# hv_io_rms.net
KiCad netlist of a schematic drawn in Altium Designer
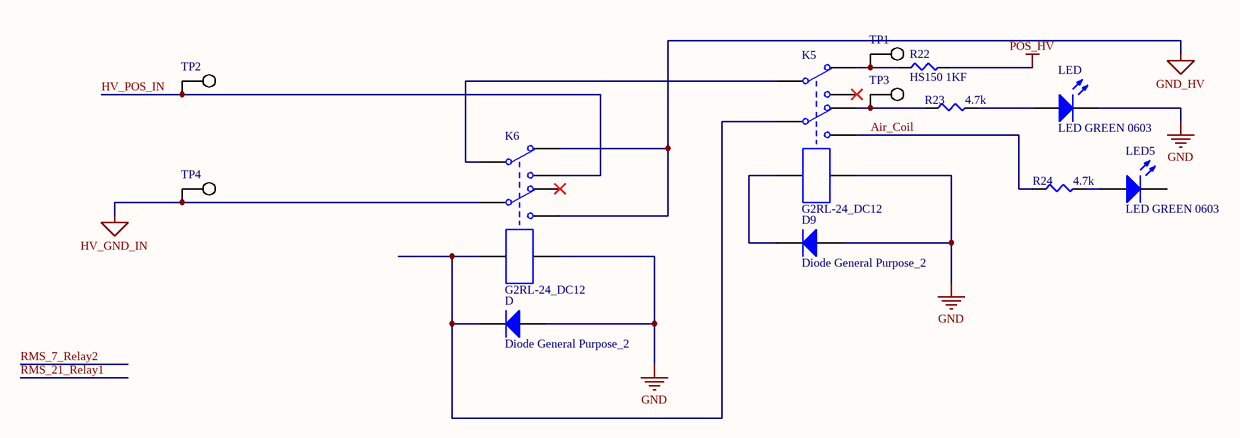
[diagram p0: hv_io_rms.SchDoc]

(export (version "E")
  (design (tool "Eeschema 10.0.6"))
  (components
    (comp (ref "D")
      (value "Diode General Purpose_2")
      (footprint "SODFL250X110-2N")
      (description "DIODE GEN PURP 20V 350MA SOD323")
      (fields (field (name "MANUFACTURER") "Diodes Incorporated"))
      (libsource (lib "misc") (part "Diode General Purpose_2"))
    )
    (comp (ref "D9")
      (value "Diode General Purpose_2")
      (footprint "SODFL250X110-2N")
      (description "DIODE GEN PURP 20V 350MA SOD323")
      (fields (field (name "MANUFACTURER") "Diodes Incorporated"))
      (libsource (lib "misc") (part "Diode General Purpose_2"))
    )
    (comp (ref "K5")
      (value "G2RL-24_DC12")
      (description "RELAY GEN PURPOSE DPDT 8A 12V")
      (fields (field (name "MANUFACTURER") "Omron Electronics"))
      (libsource (lib "temp") (part "G2RL-24_DC12"))
    )
    (comp (ref "K6")
      (value "G2RL-24_DC12")
      (description "RELAY GEN PURPOSE DPDT 8A 12V")
      (fields (field (name "MANUFACTURER") "Omron Electronics"))
      (libsource (lib "temp") (part "G2RL-24_DC12"))
    )
    (comp (ref "LED")
      (value "LED GREEN 0603")
      (footprint "LED 0603 GREEN")
      (fields (field (name "MANUFACTURER") "Lite-On Inc."))
      (libsource (lib "misc") (part "LED GREEN 0603"))
    )
    (comp (ref "LED5")
      (value "LED GREEN 0603")
      (footprint "LED 0603 GREEN")
      (fields (field (name "MANUFACTURER") "Lite-On Inc."))
      (libsource (lib "misc") (part "LED GREEN 0603"))
    )
    (comp (ref "R22")
      (value "HS150 1KF")
      (footprint "HS150 1KF")
      (description "1K Power Resistor")
      (fields (field (name "MANUFACTURER") "Ohmite"))
      (libsource (lib "temp") (part "HS150 1KF"))
    )
    (comp (ref "R23")
      (value "4.7k")
      (footprint "SMD-0402-RES")
      (description "RES SMD 4.7K OHM 5% 1/10W 0402")
      (fields (field (name "PART NUMBER") "ERJ-2GEJ472X") (field (name "DIGI-KEY PART NUMBER") "P4.7KJCT-ND"))
      (libsource (lib "resistor") (part "ERJ-2GEJ472X"))
    )
    (comp (ref "R24")
      (value "4.7k")
      (footprint "SMD-0402-RES")
      (description "RES SMD 4.7K OHM 5% 1/10W 0402")
      (fields (field (name "PART NUMBER") "ERJ-2GEJ472X") (field (name "DIGI-KEY PART NUMBER") "P4.7KJCT-ND"))
      (libsource (lib "resistor") (part "ERJ-2GEJ472X"))
    )
    (comp (ref "TP1")
      (value "TP2")
      (footprint "Test Point")
      (description "Test Point")
      (libsource (lib "temp") (part "TP2"))
    )
    (comp (ref "TP2")
      (value "TP2")
      (footprint "Test Point")
      (description "Test Point")
      (libsource (lib "temp") (part "TP2"))
    )
    (comp (ref "TP3")
      (value "TP2")
      (footprint "Test Point")
      (description "Test Point")
      (libsource (lib "temp") (part "TP2"))
    )
    (comp (ref "TP4")
      (value "TP2")
      (footprint "Test Point")
      (description "Test Point")
      (libsource (lib "temp") (part "TP2"))
    )
  )
  (nets
    (net (code "1") (name "/Air_Coil") (class "Default")
      (node (ref "K5") (pin "6") (pinfunction "6_6") (pintype "passive"))
      (node (ref "R24") (pin "1") (pinfunction "1_1") (pintype "passive"))
    )
    (net (code "2") (name "/HV_POS_IN") (class "Default")
      (node (ref "K6") (pin "3") (pinfunction "3_3") (pintype "passive"))
      (node (ref "TP2") (pin "1") (pinfunction "1_1") (pintype "passive"))
    )
    (net (code "5") (name "GND") (class "Default")
      (node (ref "D") (pin "1") (pinfunction "A_1") (pintype "passive"))
      (node (ref "D9") (pin "1") (pinfunction "A_1") (pintype "passive"))
      (node (ref "K5") (pin "8") (pinfunction "8_8") (pintype "passive"))
      (node (ref "K6") (pin "8") (pinfunction "8_8") (pintype "passive"))
      (node (ref "LED") (pin "2") (pinfunction "K_2") (pintype "passive"))
    )
    (net (code "6") (name "GND_HV") (class "Default")
      (node (ref "K6") (pin "2") (pinfunction "2_2") (pintype "passive"))
      (node (ref "K6") (pin "6") (pinfunction "6_6") (pintype "passive"))
    )
    (net (code "7") (name "HV_GND_IN") (class "Default")
      (node (ref "K6") (pin "4") (pinfunction "4_4") (pintype "passive"))
      (node (ref "TP4") (pin "1") (pinfunction "1_1") (pintype "passive"))
    )
    (net (code "8") (name "Net-(D-K)") (class "Default")
      (node (ref "D") (pin "2") (pinfunction "K_2") (pintype "passive"))
      (node (ref "K5") (pin "4") (pinfunction "4_4") (pintype "passive"))
      (node (ref "K6") (pin "7") (pinfunction "7_7") (pintype "passive"))
    )
    (net (code "9") (name "Net-(D9-K)") (class "Default")
      (node (ref "D9") (pin "2") (pinfunction "K_2") (pintype "passive"))
      (node (ref "K5") (pin "7") (pinfunction "7_7") (pintype "passive"))
    )
    (net (code "10") (name "Net-(K5-Pad1)") (class "Default")
      (node (ref "K5") (pin "1") (pinfunction "1_1") (pintype "passive"))
      (node (ref "K6") (pin "1") (pinfunction "1_1") (pintype "passive"))
    )
    (net (code "11") (name "Net-(K5-Pad2)") (class "Default")
      (node (ref "K5") (pin "2") (pinfunction "2_2") (pintype "passive"))
      (node (ref "R22") (pin "1") (pinfunction "1_1") (pintype "passive"))
      (node (ref "TP1") (pin "1") (pinfunction "1_1") (pintype "passive"))
    )
    (net (code "12") (name "Net-(K5-Pad5)") (class "Default")
      (node (ref "K5") (pin "5") (pinfunction "5_5") (pintype "passive"))
      (node (ref "R23") (pin "1") (pinfunction "1_1") (pintype "passive"))
      (node (ref "TP3") (pin "1") (pinfunction "1_1") (pintype "passive"))
    )
    (net (code "13") (name "Net-(LED-A)") (class "Default")
      (node (ref "LED") (pin "1") (pinfunction "A_1") (pintype "passive"))
      (node (ref "R23") (pin "2") (pinfunction "2_2") (pintype "passive"))
    )
    (net (code "14") (name "Net-(LED5-A)") (class "Default")
      (node (ref "LED5") (pin "1") (pinfunction "A_1") (pintype "passive"))
      (node (ref "R24") (pin "2") (pinfunction "2_2") (pintype "passive"))
    )
    (net (code "15") (name "POS_HV") (class "Default")
      (node (ref "R22") (pin "2") (pinfunction "2_2") (pintype "passive"))
    )
    (net (code "16") (name "unconnected-(K5-Pad3)") (class "Default")
      (node (ref "K5") (pin "3") (pinfunction "3_3") (pintype "passive+no_connect"))
    )
    (net (code "17") (name "unconnected-(K6-Pad5)") (class "Default")
      (node (ref "K6") (pin "5") (pinfunction "5_5") (pintype "passive+no_connect"))
    )
    (net (code "18") (name "unconnected-(LED5-K-Pad2)") (class "Default")
      (node (ref "LED5") (pin "2") (pinfunction "K_2") (pintype "passive"))
    )
  )
)
